# gateway.net
KiCad netlist of a schematic drawn in Altium Designer
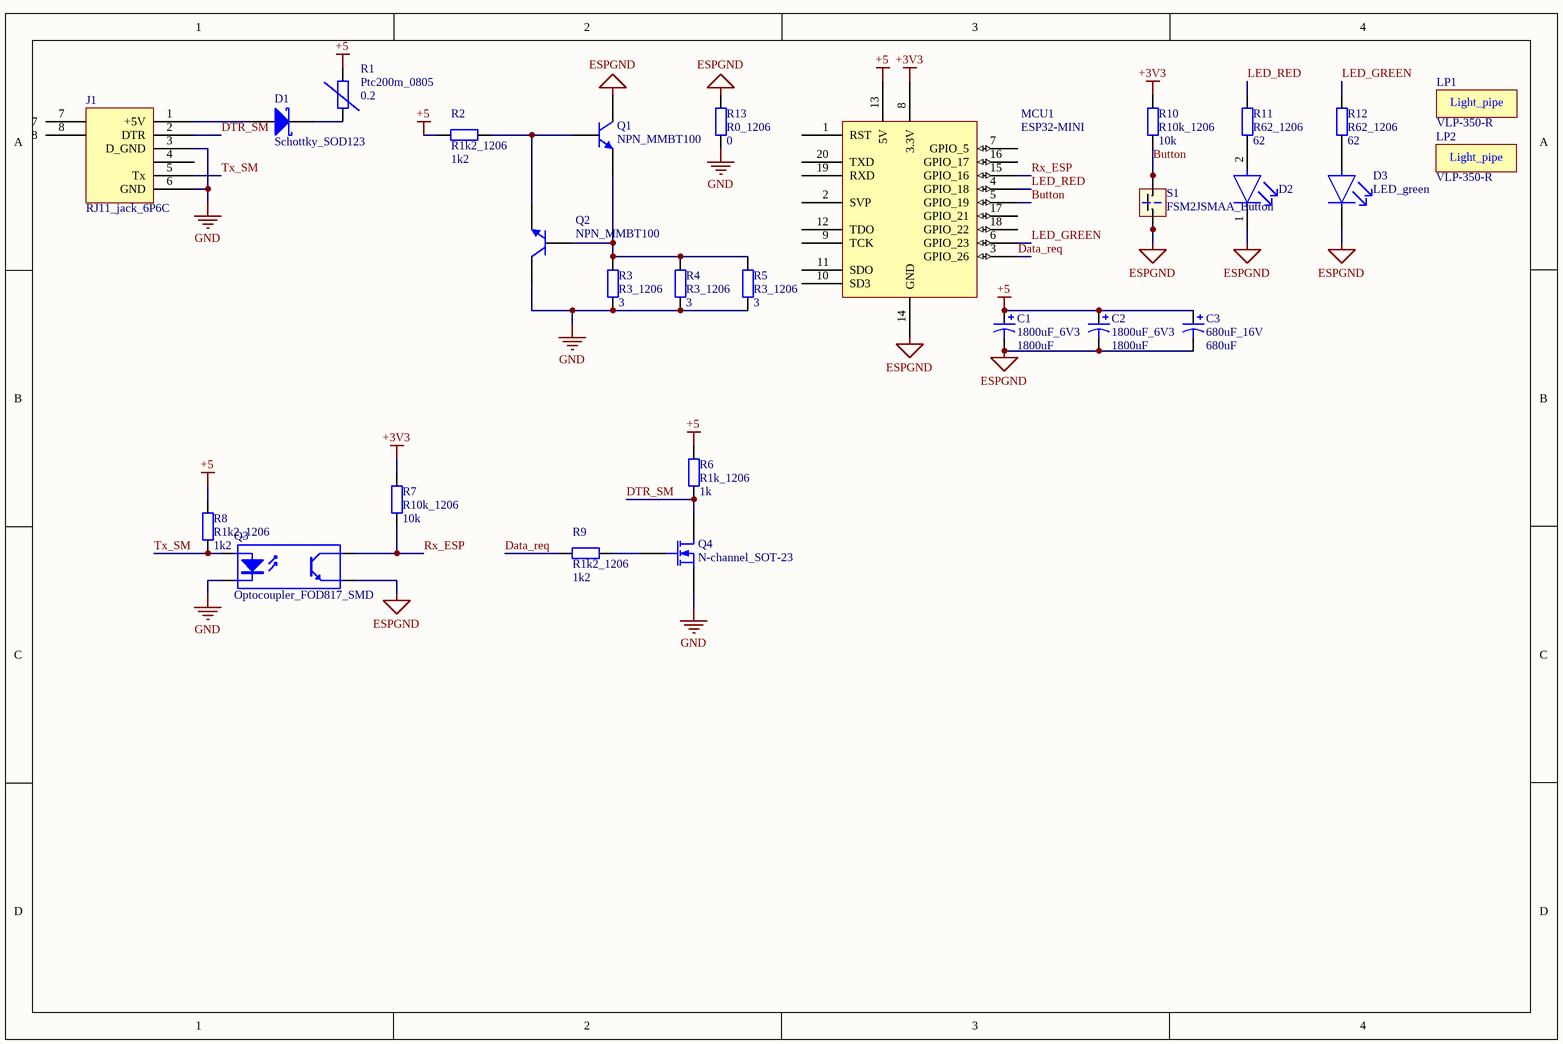
[diagram p0: gateway.SchDoc]

(export (version "E")
  (design (tool "Eeschema 10.0.6"))
  (components
    (comp (ref "C1")
      (value "1800uF_6V3")
      (footprint "CAPAE109103X105M_680uF")
      (description "SMD Aluminium Electrolytic Capacitor, Radial Can, 1800 µF, 10 V, 0.092 ohm, TRV Series")
      (fields
        (field (name "MANUFACTURER PART NUMBER") "EEE-FN0J182UV")
        (field (name "MANUFACTURER") "Panasonic")
        (field (name "ALTIUM_VALUE") "1800uF")
      )
      (libsource (lib "Capacitor") (part "1800uF_6V3"))
    )
    (comp (ref "C2")
      (value "1800uF_6V3")
      (footprint "CAPAE109103X105M_680uF")
      (description "SMD Aluminium Electrolytic Capacitor, Radial Can, 1800 µF, 10 V, 0.092 ohm, TRV Series")
      (fields
        (field (name "MANUFACTURER PART NUMBER") "EEE-FN0J182UV")
        (field (name "MANUFACTURER") "Panasonic")
        (field (name "ALTIUM_VALUE") "1800uF")
      )
      (libsource (lib "Capacitor") (part "1800uF_6V3"))
    )
    (comp (ref "C3")
      (value "680uF_16V")
      (footprint "CAPAE109103X105M_680uF")
      (description "Aluminum Electrolytic Capacitors - SMD LOW ESR ELECTROLYTIC CAPACITORS")
      (fields
        (field (name "MANUFACTURER PART NUMBER") "16TZV680M10X10.5")
        (field (name "MANUFACTURER") "Rubycon")
        (field (name "ALTIUM_VALUE") "680uF")
      )
      (libsource (lib "Capacitor") (part "680uF_16V"))
    )
    (comp (ref "D1")
      (value "Schottky_SOD123")
      (footprint "Diode_SOD-123")
      (description "Schottky Rectifier, 20 V, 500 mA, Single, SOD-123, 2 Pins, 320 mV")
      (fields
        (field (name "MANUFACTURER PART NUMBER") "STPS0520Z")
        (field (name "MANUFACTURER") "STMicroelectronics")
      )
      (libsource (lib "Diodes") (part "Schottky_SOD123"))
    )
    (comp (ref "D2")
      (value "red led")
      (footprint "Kingbright_KPT-2012EC_0")
      (description "KPT-2012EC -  LED, Low Power, Red, SMD, 0805 [2012 Metric], 30 mA, 2 V, 617 nm")
      (fields
        (field (name "MANUFACTURER PART NUMBER") "AP2012SRCPRV")
        (field (name "MANUFACTURER") "Kingbright")
      )
      (libsource (lib "Button_led") (part "KPT-2012EC"))
    )
    (comp (ref "D3")
      (value "LED_green")
      (footprint "Kingbright_KPT-2012EC_0")
      (description "Standard LEDs - SMD GRN WATER CLEAR 0805")
      (fields
        (field (name "MANUFACTURER") "Kingbright")
        (field (name "MANUFACTURER PART NUMBER") "AP2012MGC")
      )
      (libsource (lib "Button_led") (part "LED_green"))
    )
    (comp (ref "J1")
      (value "RJ11_jack_6P6C")
      (footprint "44144-0005")
      (description "Modular Connector, RJ11 Jack, 1 x 1 (Port), 6P6C, Cat3, Surface Mount")
      (fields (field (name "MANUFACTURER PART NUMBER") "44144-0005") (field (name "MANUFACTURER") "Molex"))
      (libsource (lib "Connectors") (part "RJ11_jack_6P6C"))
    )
    (comp (ref "LP1")
      (value "VLP-350-R")
      (footprint "VLP-350-R")
      (description "LIGHT PIPE, SINGLE, ROUND, PCB")
      (fields (field (name "MANUFACTURER") "BIVAR"))
      (libsource (lib "Button_led") (part "VLP-350-R"))
    )
    (comp (ref "LP2")
      (value "VLP-350-R")
      (footprint "VLP-350-R")
      (description "LIGHT PIPE, SINGLE, ROUND, PCB")
      (fields (field (name "MANUFACTURER") "BIVAR"))
      (libsource (lib "Button_led") (part "VLP-350-R"))
    )
    (comp (ref "MCU1")
      (value "ESP32-MINI")
      (footprint "PINHEADERS_SMD_10")
      (description "LilyGO TTGO T7 Mini32 V1.4 ESP32-WROVER")
      (fields (field (name "MANUFACTURER PART NUMBER") "10129380-910002ALF"))
      (libsource (lib "mcu") (part "ESP32-MINI"))
    )
    (comp (ref "Q1")
      (value "NPN_MMBT100")
      (footprint "SOT95P245X110-3N")
      (description "Bipolar (BJT) Single Transistor, NPN, 45 V, 500 mA, 350 mW, SOT-23, Surface Mount")
      (fields
        (field (name "MANUFACTURER PART NUMBER") "MMBT100")
        (field (name "MANUFACTURER") "ON Semiconductor / Fairchild")
      )
      (libsource (lib "Transistor") (part "NPN_MMBT100"))
    )
    (comp (ref "Q2")
      (value "NPN_MMBT100")
      (footprint "SOT95P245X110-3N")
      (description "Bipolar (BJT) Single Transistor, NPN, 45 V, 500 mA, 350 mW, SOT-23, Surface Mount")
      (fields
        (field (name "MANUFACTURER PART NUMBER") "MMBT100")
        (field (name "MANUFACTURER") "ON Semiconductor / Fairchild")
      )
      (libsource (lib "Transistor") (part "NPN_MMBT100"))
    )
    (comp (ref "Q3")
      (value "Optocoupler_FOD817_SMD")
      (footprint "FOD814_DIPSMD")
      (description "Optocoupler, Transistor Output, 1 Channel, Surface Mount DIP, 4 Pins, 50 mA, 5 kV, 200 %")
      (fields
        (field (name "MANUFACTURER PART NUMBER") "FOD817C3SD")
        (field (name "MANUFACTURER") "ON Semiconductor / Fairchild")
      )
      (libsource (lib "Transistor") (part "Optocoupler_FOD817_SMD"))
    )
    (comp (ref "Q4")
      (value "N-channel_SOT-23")
      (footprint "SOT95P237X110-3N")
      (description "Power MOSFET, N Channel, 60 V, 260 mA, 1 ohm, SOT-23, Surface Mount")
      (fields
        (field (name "MANUFACTURER PART NUMBER") "NTR5103NT1G")
        (field (name "MANUFACTURER") "ON Semiconductor")
      )
      (libsource (lib "Mosfet") (part "N-channel_SOT-23"))
    )
    (comp (ref "R1")
      (value "Ptc200m_0805")
      (footprint "R0805")
      (description "Thermistor, PTC, SMD, 0805, 0.2 OHM")
      (fields
        (field (name "MANUFACTURER PART NUMBER") "PRG21BC0R2MM1RA")
        (field (name "MANUFACTURER") "Murata")
        (field (name "ALTIUM_VALUE") "0.2")
      )
      (libsource (lib "Resistor") (part "Ptc200m_0805"))
    )
    (comp (ref "R2")
      (value "R1k2_1206")
      (footprint "R1206")
      (description "Thick Film Resistors - SMD 1206 1.2Kohms 1% AEC-Q200")
      (fields
        (field (name "MANUFACTURER") "Panasonic")
        (field (name "MANUFACTURER PART NUMBER") "ERJ-8ENF1201V")
        (field (name "ALTIUM_VALUE") "1k2")
      )
      (libsource (lib "Resistor") (part "R1k2_1206"))
    )
    (comp (ref "R3")
      (value "R3_1206")
      (footprint "R1206")
      (description "Current Sense Resistors - SMD 1206 3.0ohm 1% Curr Sense AEC-Q200")
      (fields
        (field (name "MANUFACTURER PART NUMBER") "ERJ8RQF3R0V")
        (field (name "MANUFACTURER") "Panasonic")
        (field (name "ALTIUM_VALUE") "3")
      )
      (libsource (lib "Resistor") (part "R3_1206"))
    )
    (comp (ref "R4")
      (value "R3_1206")
      (footprint "R1206")
      (description "Current Sense Resistors - SMD 1206 3.0ohm 1% Curr Sense AEC-Q200")
      (fields
        (field (name "MANUFACTURER PART NUMBER") "ERJ8RQF3R0V")
        (field (name "MANUFACTURER") "Panasonic")
        (field (name "ALTIUM_VALUE") "3")
      )
      (libsource (lib "Resistor") (part "R3_1206"))
    )
    (comp (ref "R5")
      (value "R3_1206")
      (footprint "R1206")
      (description "Current Sense Resistors - SMD 1206 3.0ohm 1% Curr Sense AEC-Q200")
      (fields
        (field (name "MANUFACTURER PART NUMBER") "ERJ8RQF3R0V")
        (field (name "MANUFACTURER") "Panasonic")
        (field (name "ALTIUM_VALUE") "3")
      )
      (libsource (lib "Resistor") (part "R3_1206"))
    )
    (comp (ref "R6")
      (value "R1k_1206")
      (footprint "R1206")
      (description "Thick Film Resistors - SMD 1206 1Kohms 1% Tol AEC-Q200")
      (fields
        (field (name "TOLERANCE") "1%")
        (field (name "MANUFACTURER PART NUMBER") "ERJ-8ENF1001V")
        (field (name "ALTIUM_VALUE") "1k")
      )
      (libsource (lib "Resistor") (part "R1k_1206"))
    )
    (comp (ref "R7")
      (value "R10k_1206")
      (footprint "R1206")
      (description "Thick Film Resistors - SMD 1206 10Kohms 1% AEC-Q200")
      (fields
        (field (name "TOLERANCE") "1%")
        (field (name "MANUFACTURER PART NUMBER") "ERJ-8ENF1002V")
        (field (name "ALTIUM_VALUE") "10k")
      )
      (libsource (lib "Resistor") (part "R10k_1206"))
    )
    (comp (ref "R8")
      (value "R1k2_1206")
      (footprint "R1206")
      (description "Thick Film Resistors - SMD 1206 1.2Kohms 1% AEC-Q200")
      (fields
        (field (name "MANUFACTURER") "Panasonic")
        (field (name "MANUFACTURER PART NUMBER") "ERJ-8ENF1201V")
        (field (name "ALTIUM_VALUE") "1k2")
      )
      (libsource (lib "") (part "R1k2_1206_1"))
    )
    (comp (ref "R9")
      (value "R1k2_1206")
      (footprint "R1206")
      (description "Thick Film Resistors - SMD 1206 1.2Kohms 1% AEC-Q200")
      (fields
        (field (name "MANUFACTURER") "Panasonic")
        (field (name "MANUFACTURER PART NUMBER") "ERJ-8ENF1201V")
        (field (name "ALTIUM_VALUE") "1k2")
      )
      (libsource (lib "Resistor") (part "R1k2_1206"))
    )
    (comp (ref "R10")
      (value "R10k_1206")
      (footprint "R1206")
      (description "Thick Film Resistors - SMD 1206 10Kohms 1% AEC-Q200")
      (fields
        (field (name "TOLERANCE") "1%")
        (field (name "MANUFACTURER PART NUMBER") "ERJ-8ENF1002V")
        (field (name "ALTIUM_VALUE") "10k")
      )
      (libsource (lib "Resistor") (part "R10k_1206"))
    )
    (comp (ref "R11")
      (value "R62_1206")
      (footprint "R1206")
      (description "Thick Film Resistors - SMD 1206 62ohms 1% AEC-Q200")
      (fields
        (field (name "TOLERANCE") "1%")
        (field (name "MANUFACTURER PART NUMBER") "ERJ-8ENF62R0V")
        (field (name "ALTIUM_VALUE") "62")
      )
      (libsource (lib "Resistor") (part "R62_1206"))
    )
    (comp (ref "R12")
      (value "R62_1206")
      (footprint "R1206")
      (description "Thick Film Resistors - SMD 1206 62ohms 1% AEC-Q200")
      (fields
        (field (name "TOLERANCE") "1%")
        (field (name "MANUFACTURER PART NUMBER") "ERJ-8ENF62R0V")
        (field (name "ALTIUM_VALUE") "62")
      )
      (libsource (lib "Resistor") (part "R62_1206"))
    )
    (comp (ref "R13")
      (value "R0_1206")
      (footprint "R1206")
      (fields (field (name "ALTIUM_VALUE") "0"))
      (libsource (lib "Resistor") (part "R0_1206"))
    )
    (comp (ref "S1")
      (value "FSM2JSMAA_Button")
      (footprint "FP-FSM2JSMAA-MFG")
      (description "Tactile Switch, FSMJSM Series, Top Actuated, Surface Mount, Round Button, 260 gf, 50mA at 24VDC")
      (fields
        (field (name "MANUFACTURER PART NUMBER") "FSM2JSMAA")
        (field (name "MANUFACTURER") "TE Connectivity")
      )
      (libsource (lib "Button_led") (part "FSM2JSMAA_Button"))
    )
  )
  (nets
    (net (code "1") (name "+3V3") (class "Default")
      (node (ref "MCU1") (pin "8") (pinfunction "3.3V_8") (pintype "power_in"))
      (node (ref "R10") (pin "2") (pinfunction "2_2") (pintype "passive"))
      (node (ref "R7") (pin "2") (pinfunction "2_2") (pintype "passive"))
    )
    (net (code "2") (name "+5") (class "Default")
      (node (ref "C1") (pin "1") (pinfunction "1_1") (pintype "passive"))
      (node (ref "C2") (pin "1") (pinfunction "1_1") (pintype "passive"))
      (node (ref "C3") (pin "1") (pinfunction "1_1") (pintype "passive"))
      (node (ref "MCU1") (pin "13") (pinfunction "5V_13") (pintype "power_in"))
      (node (ref "R1") (pin "2") (pinfunction "2_2") (pintype "passive"))
      (node (ref "R2") (pin "1") (pinfunction "1_1") (pintype "passive"))
      (node (ref "R6") (pin "2") (pinfunction "2_2") (pintype "passive"))
      (node (ref "R8") (pin "2") (pinfunction "2_2") (pintype "passive"))
    )
    (net (code "3") (name "/Button") (class "Default")
      (node (ref "MCU1") (pin "5") (pinfunction "GPIO_19_5") (pintype "bidirectional"))
      (node (ref "R10") (pin "1") (pinfunction "1_1") (pintype "passive"))
      (node (ref "S1") (pin "2") (pinfunction "b_2") (pintype "passive"))
      (node (ref "S1") (pin "4") (pinfunction "d_4") (pintype "passive"))
    )
    (net (code "4") (name "/DTR_SM") (class "Default")
      (node (ref "J1") (pin "2") (pinfunction "DTR_2") (pintype "passive"))
      (node (ref "Q4") (pin "1") (pinfunction "D_1") (pintype "passive"))
      (node (ref "R6") (pin "1") (pinfunction "1_1") (pintype "passive"))
    )
    (net (code "5") (name "/Data_req") (class "Default")
      (node (ref "MCU1") (pin "3") (pinfunction "GPIO_26_3") (pintype "bidirectional"))
      (node (ref "R9") (pin "1") (pinfunction "1_1") (pintype "passive"))
    )
    (net (code "6") (name "/LED_GREEN") (class "Default")
      (node (ref "MCU1") (pin "6") (pinfunction "GPIO_23_6") (pintype "bidirectional"))
      (node (ref "R12") (pin "2") (pinfunction "2_2") (pintype "passive"))
    )
    (net (code "7") (name "/LED_RED") (class "Default")
      (node (ref "MCU1") (pin "4") (pinfunction "GPIO_18_4") (pintype "bidirectional"))
      (node (ref "R11") (pin "2") (pinfunction "2_2") (pintype "passive"))
    )
    (net (code "8") (name "/Rx_ESP") (class "Default")
      (node (ref "MCU1") (pin "15") (pinfunction "GPIO_16_15") (pintype "bidirectional"))
      (node (ref "Q3") (pin "4") (pinfunction "C_4") (pintype "passive"))
      (node (ref "R7") (pin "1") (pinfunction "1_1") (pintype "passive"))
    )
    (net (code "9") (name "/Tx_SM") (class "Default")
      (node (ref "J1") (pin "5") (pinfunction "Tx_5") (pintype "passive"))
      (node (ref "Q3") (pin "1") (pinfunction "A_1") (pintype "passive"))
      (node (ref "R8") (pin "1") (pinfunction "1_1") (pintype "passive"))
    )
    (net (code "10") (name "ESPGND") (class "Default")
      (node (ref "C1") (pin "2") (pinfunction "2_2") (pintype "passive"))
      (node (ref "C2") (pin "2") (pinfunction "2_2") (pintype "passive"))
      (node (ref "C3") (pin "2") (pinfunction "2_2") (pintype "passive"))
      (node (ref "D2") (pin "1") (pinfunction "C_1") (pintype "passive"))
      (node (ref "D3") (pin "1") (pinfunction "C_1") (pintype "passive"))
      (node (ref "MCU1") (pin "14") (pinfunction "GND_14") (pintype "power_in"))
      (node (ref "Q1") (pin "3") (pinfunction "C_3") (pintype "passive"))
      (node (ref "Q3") (pin "3") (pinfunction "E_3") (pintype "passive"))
      (node (ref "R13") (pin "2") (pinfunction "2_2") (pintype "passive"))
      (node (ref "S1") (pin "1") (pinfunction "a_1") (pintype "passive"))
      (node (ref "S1") (pin "3") (pinfunction "c_3") (pintype "passive"))
    )
    (net (code "11") (name "GND") (class "Default")
      (node (ref "J1") (pin "3") (pinfunction "D_GND_3") (pintype "power_in"))
      (node (ref "J1") (pin "6") (pinfunction "GND_6") (pintype "power_in"))
      (node (ref "Q2") (pin "3") (pinfunction "C_3") (pintype "passive"))
      (node (ref "Q3") (pin "2") (pinfunction "K_2") (pintype "passive"))
      (node (ref "Q4") (pin "3") (pinfunction "S_3") (pintype "passive"))
      (node (ref "R13") (pin "1") (pinfunction "1_1") (pintype "passive"))
      (node (ref "R3") (pin "1") (pinfunction "1_1") (pintype "passive"))
      (node (ref "R4") (pin "1") (pinfunction "1_1") (pintype "passive"))
      (node (ref "R5") (pin "1") (pinfunction "1_1") (pintype "passive"))
    )
    (net (code "12") (name "Net-(D1-A)") (class "Default")
      (node (ref "D1") (pin "2") (pinfunction "A_2") (pintype "passive"))
      (node (ref "J1") (pin "1") (pinfunction "+5V_1") (pintype "power_in"))
    )
    (net (code "13") (name "Net-(D1-K)") (class "Default")
      (node (ref "D1") (pin "1") (pinfunction "K_1") (pintype "passive"))
      (node (ref "R1") (pin "1") (pinfunction "1_1") (pintype "passive"))
    )
    (net (code "14") (name "Net-(D2-A)") (class "Default")
      (node (ref "D2") (pin "2") (pinfunction "A_2") (pintype "passive"))
      (node (ref "R11") (pin "1") (pinfunction "1_1") (pintype "passive"))
    )
    (net (code "15") (name "Net-(D3-A)") (class "Default")
      (node (ref "D3") (pin "2") (pinfunction "A_2") (pintype "passive"))
      (node (ref "R12") (pin "1") (pinfunction "1_1") (pintype "passive"))
    )
    (net (code "16") (name "Net-(Q1-B)") (class "Default")
      (node (ref "Q1") (pin "2") (pinfunction "B_2") (pintype "passive"))
      (node (ref "Q2") (pin "1") (pinfunction "E_1") (pintype "passive"))
      (node (ref "R2") (pin "2") (pinfunction "2_2") (pintype "passive"))
    )
    (net (code "17") (name "Net-(Q1-E)") (class "Default")
      (node (ref "Q1") (pin "1") (pinfunction "E_1") (pintype "passive"))
      (node (ref "Q2") (pin "2") (pinfunction "B_2") (pintype "passive"))
      (node (ref "R3") (pin "2") (pinfunction "2_2") (pintype "passive"))
      (node (ref "R4") (pin "2") (pinfunction "2_2") (pintype "passive"))
      (node (ref "R5") (pin "2") (pinfunction "2_2") (pintype "passive"))
    )
    (net (code "18") (name "Net-(Q4-G)") (class "Default")
      (node (ref "Q4") (pin "2") (pinfunction "G_2") (pintype "passive"))
      (node (ref "R9") (pin "2") (pinfunction "2_2") (pintype "passive"))
    )
    (net (code "19") (name "unconnected-(J1-Pad4)") (class "Default")
      (node (ref "J1") (pin "4") (pintype "passive"))
    )
    (net (code "20") (name "unconnected-(J1-Pad7)") (class "Default")
      (node (ref "J1") (pin "7") (pinfunction "7_7") (pintype "passive"))
    )
    (net (code "21") (name "unconnected-(J1-Pad8)") (class "Default")
      (node (ref "J1") (pin "8") (pinfunction "8_8") (pintype "passive"))
    )
    (net (code "22") (name "unconnected-(MCU1-GPIO_5-Pad7)") (class "Default")
      (node (ref "MCU1") (pin "7") (pinfunction "GPIO_5_7") (pintype "bidirectional"))
    )
    (net (code "23") (name "unconnected-(MCU1-GPIO_17-Pad16)") (class "Default")
      (node (ref "MCU1") (pin "16") (pinfunction "GPIO_17_16") (pintype "bidirectional"))
    )
    (net (code "24") (name "unconnected-(MCU1-GPIO_21-Pad17)") (class "Default")
      (node (ref "MCU1") (pin "17") (pinfunction "GPIO_21_17") (pintype "bidirectional"))
    )
    (net (code "25") (name "unconnected-(MCU1-GPIO_22-Pad18)") (class "Default")
      (node (ref "MCU1") (pin "18") (pinfunction "GPIO_22_18") (pintype "bidirectional"))
    )
    (net (code "26") (name "unconnected-(MCU1-RST-Pad1)") (class "Default")
      (node (ref "MCU1") (pin "1") (pinfunction "RST_1") (pintype "passive"))
    )
    (net (code "27") (name "unconnected-(MCU1-RXD-Pad19)") (class "Default")
      (node (ref "MCU1") (pin "19") (pinfunction "RXD_19") (pintype "passive"))
    )
    (net (code "28") (name "unconnected-(MCU1-SD3-Pad10)") (class "Default")
      (node (ref "MCU1") (pin "10") (pinfunction "SD3_10") (pintype "passive"))
    )
    (net (code "29") (name "unconnected-(MCU1-SDO-Pad11)") (class "Default")
      (node (ref "MCU1") (pin "11") (pinfunction "SDO_11") (pintype "passive"))
    )
    (net (code "30") (name "unconnected-(MCU1-SVP-Pad2)") (class "Default")
      (node (ref "MCU1") (pin "2") (pinfunction "SVP_2") (pintype "passive"))
    )
    (net (code "31") (name "unconnected-(MCU1-TCK-Pad9)") (class "Default")
      (node (ref "MCU1") (pin "9") (pinfunction "TCK_9") (pintype "passive"))
    )
    (net (code "32") (name "unconnected-(MCU1-TDO-Pad12)") (class "Default")
      (node (ref "MCU1") (pin "12") (pinfunction "TDO_12") (pintype "passive"))
    )
    (net (code "33") (name "unconnected-(MCU1-TXD-Pad20)") (class "Default")
      (node (ref "MCU1") (pin "20") (pinfunction "TXD_20") (pintype "passive"))
    )
  )
)
